# thingy.net
KiCad netlist of a schematic drawn in EAGLE
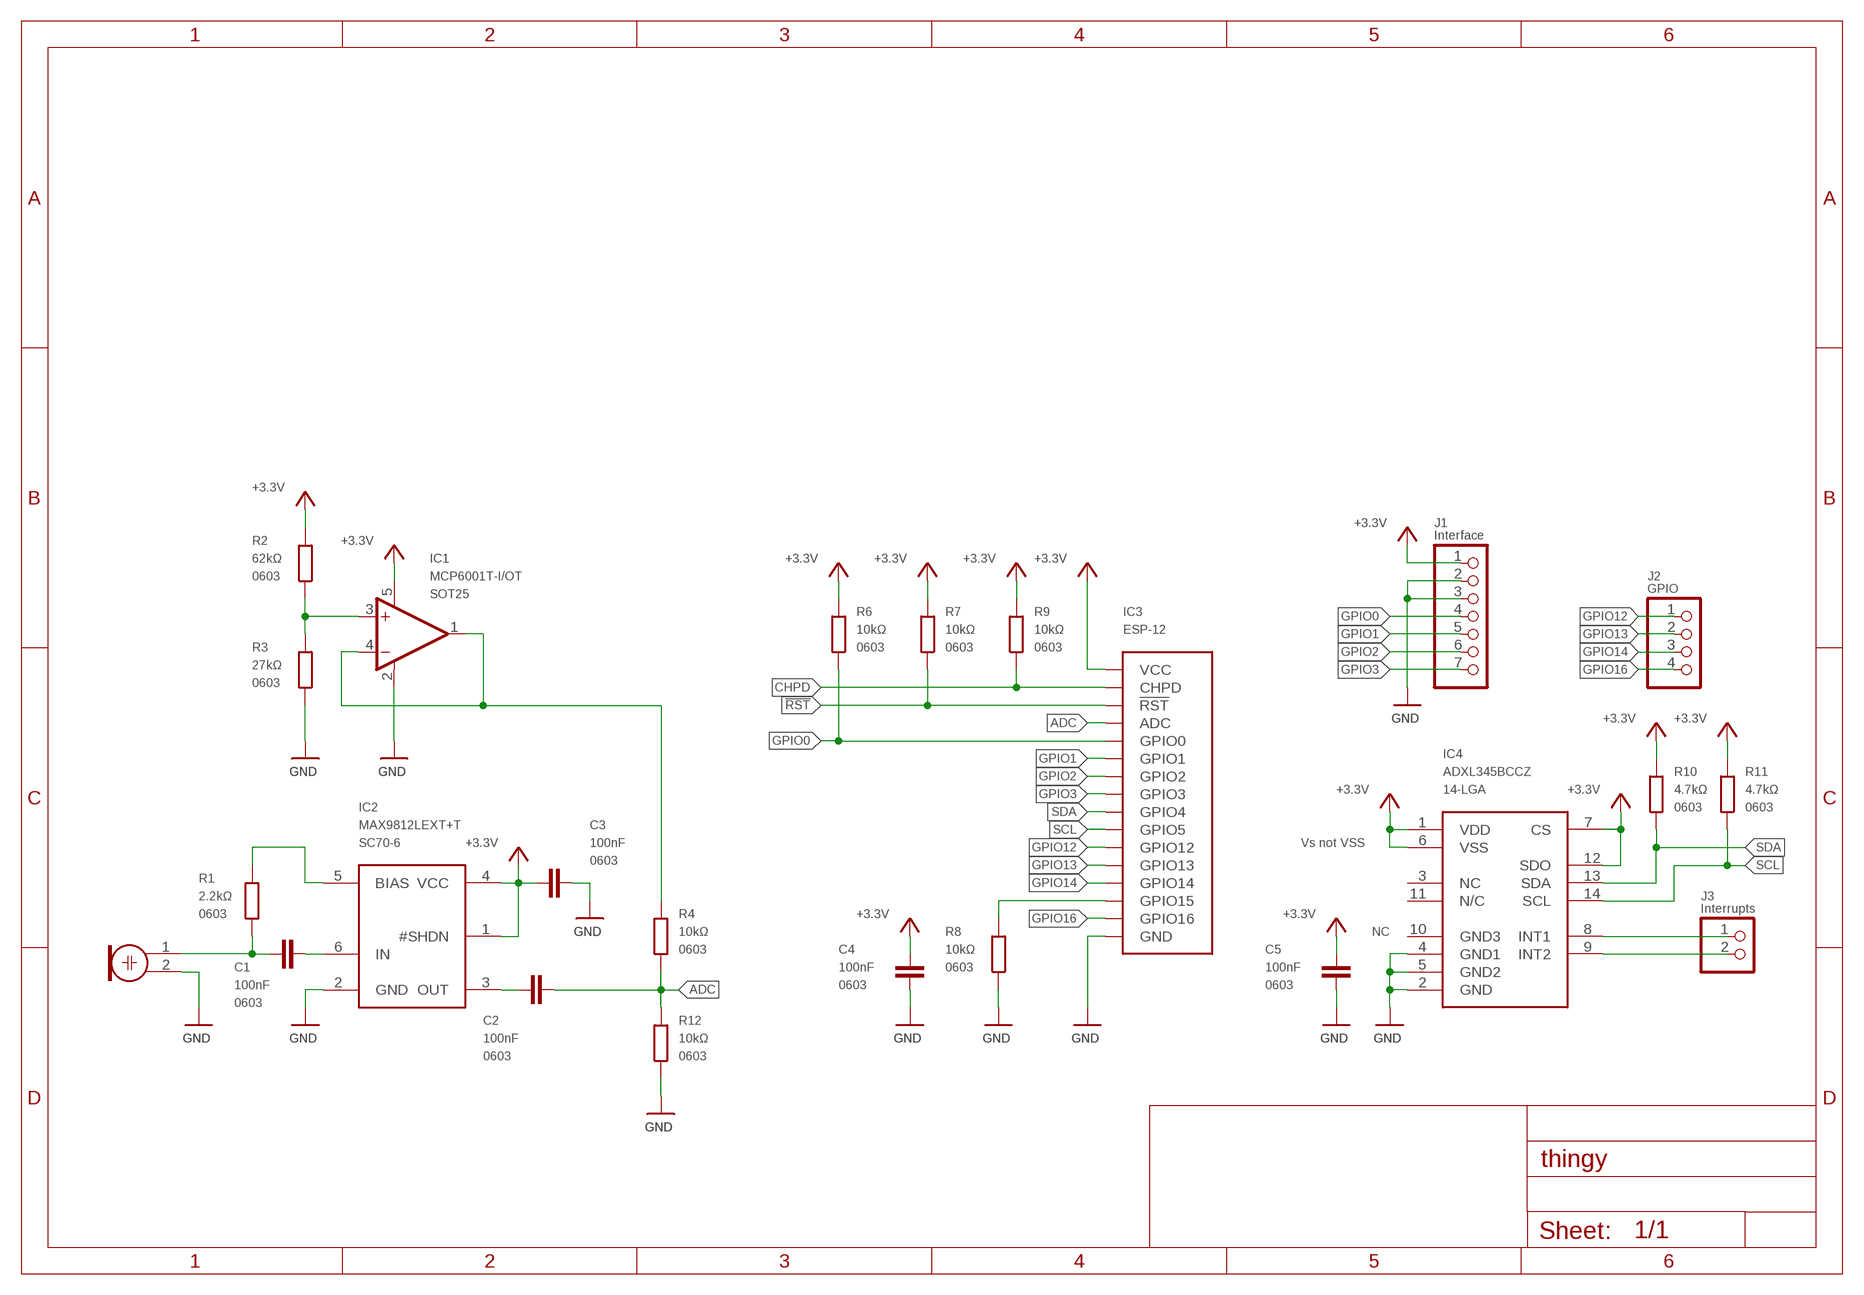
[diagram p0: schematic, sheet 1]

(export (version "E")
  (design (tool "Eeschema 10.0.6"))
  (components
    (comp (ref "C1")
      (value "100nF")
      (footprint "eagle-import:0603")
      (fields (field (name "PACKAGE") "0603"))
      (libsource (lib "eagle-import") (part "C0603"))
    )
    (comp (ref "C2")
      (value "100nF")
      (footprint "eagle-import:0603")
      (fields (field (name "PACKAGE") "0603"))
      (libsource (lib "eagle-import") (part "C0603"))
    )
    (comp (ref "C3")
      (value "100nF")
      (footprint "eagle-import:0603")
      (fields (field (name "PACKAGE") "0603"))
      (libsource (lib "eagle-import") (part "C0603"))
    )
    (comp (ref "C4")
      (value "100nF")
      (footprint "eagle-import:0603")
      (fields (field (name "PACKAGE") "0603"))
      (libsource (lib "eagle-import") (part "C0603"))
    )
    (comp (ref "C5")
      (value "100nF")
      (footprint "eagle-import:0603")
      (fields (field (name "PACKAGE") "0603"))
      (libsource (lib "eagle-import") (part "C0603"))
    )
    (comp (ref "IC1")
      (value "MCP6001T-I/OT")
      (footprint "eagle-import:SOT23-5")
      (fields (field (name "MPN") "OPA340NA/3KG4") (field (name "PACKAGE") "SOT25"))
      (libsource (lib "eagle-import") (part "OPA340N"))
    )
    (comp (ref "IC2")
      (value "MAX9812LEXT+T")
      (footprint "eagle-import:SC-70-6")
      (fields (field (name "PACKAGE") "SC70-6"))
      (libsource (lib "eagle-import") (part "MAX9812"))
    )
    (comp (ref "IC3")
      (value "ESP-12")
      (footprint "eagle-import:ESP-12")
      (libsource (lib "eagle-import") (part "ESP-12"))
    )
    (comp (ref "IC4")
      (value "ADXL345BCCZ")
      (footprint "eagle-import:LGA14")
      (fields (field (name "PACKAGE") "14-LGA"))
      (libsource (lib "eagle-import") (part "ADXL345"))
    )
    (comp (ref "J1")
      (value "Interface")
      (footprint "eagle-import:1X07")
      (libsource (lib "eagle-import") (part "PINHD-1X7"))
    )
    (comp (ref "J2")
      (value "GPIO")
      (footprint "eagle-import:1X04")
      (libsource (lib "eagle-import") (part "PINHD-1X4"))
    )
    (comp (ref "J3")
      (value "Interrupts")
      (footprint "eagle-import:1X02")
      (libsource (lib "eagle-import") (part "PINHD-1X2"))
    )
    (comp (ref "Q1")
      (value "Electret Mic")
      (footprint "eagle-import:WM-64PN")
      (libsource (lib "eagle-import") (part "ELECTRET_MICROPHON-WM.64PN"))
    )
    (comp (ref "R1")
      (value "2.2kΩ")
      (footprint "eagle-import:0603")
      (fields (field (name "PACKAGE") "0603"))
      (libsource (lib "eagle-import") (part "R0603"))
    )
    (comp (ref "R2")
      (value "62kΩ")
      (footprint "eagle-import:0603")
      (fields (field (name "PACKAGE") "0603"))
      (libsource (lib "eagle-import") (part "R0603"))
    )
    (comp (ref "R3")
      (value "27kΩ")
      (footprint "eagle-import:0603")
      (fields (field (name "PACKAGE") "0603"))
      (libsource (lib "eagle-import") (part "R0603"))
    )
    (comp (ref "R4")
      (value "10kΩ")
      (footprint "eagle-import:0603")
      (fields (field (name "PACKAGE") "0603"))
      (libsource (lib "eagle-import") (part "R0603"))
    )
    (comp (ref "R6")
      (value "10kΩ")
      (footprint "eagle-import:0603")
      (fields (field (name "PACKAGE") "0603"))
      (libsource (lib "eagle-import") (part "R0603"))
    )
    (comp (ref "R7")
      (value "10kΩ")
      (footprint "eagle-import:0603")
      (fields (field (name "PACKAGE") "0603"))
      (libsource (lib "eagle-import") (part "R0603"))
    )
    (comp (ref "R8")
      (value "10kΩ")
      (footprint "eagle-import:0603")
      (fields (field (name "PACKAGE") "0603"))
      (libsource (lib "eagle-import") (part "R0603"))
    )
    (comp (ref "R9")
      (value "10kΩ")
      (footprint "eagle-import:0603")
      (fields (field (name "PACKAGE") "0603"))
      (libsource (lib "eagle-import") (part "R0603"))
    )
    (comp (ref "R10")
      (value "4.7kΩ")
      (footprint "eagle-import:0603")
      (fields (field (name "PACKAGE") "0603"))
      (libsource (lib "eagle-import") (part "R0603"))
    )
    (comp (ref "R11")
      (value "4.7kΩ")
      (footprint "eagle-import:0603")
      (fields (field (name "PACKAGE") "0603"))
      (libsource (lib "eagle-import") (part "R0603"))
    )
    (comp (ref "R12")
      (value "10kΩ")
      (footprint "eagle-import:0603")
      (fields (field (name "PACKAGE") "0603"))
      (libsource (lib "eagle-import") (part "R0603"))
    )
  )
  (nets
    (net (code "1") (name "+3.3V") (class "Default")
      (node (ref "C3") (pin "1") (pinfunction "1_1") (pintype "passive"))
      (node (ref "C4") (pin "1") (pinfunction "1_1") (pintype "passive"))
      (node (ref "C5") (pin "1") (pinfunction "1_1") (pintype "passive"))
      (node (ref "IC1") (pin "5") (pinfunction "V+_5") (pintype "power_in"))
      (node (ref "IC2") (pin "1") (pinfunction "#SHDN_1") (pintype "input"))
      (node (ref "IC2") (pin "4") (pinfunction "VCC_4") (pintype "power_in"))
      (node (ref "IC3") (pin "VCC") (pinfunction "VCC_VCC") (pintype "bidirectional"))
      (node (ref "IC4") (pin "1") (pinfunction "VDD_1") (pintype "bidirectional"))
      (node (ref "IC4") (pin "12") (pinfunction "SDO_12") (pintype "bidirectional"))
      (node (ref "IC4") (pin "6") (pinfunction "VSS_6") (pintype "bidirectional"))
      (node (ref "IC4") (pin "7") (pinfunction "CS_7") (pintype "bidirectional"))
      (node (ref "J1") (pin "1") (pinfunction "1_1") (pintype "passive"))
      (node (ref "R10") (pin "2") (pinfunction "2_2") (pintype "passive"))
      (node (ref "R11") (pin "2") (pinfunction "2_2") (pintype "passive"))
      (node (ref "R2") (pin "2") (pinfunction "2_2") (pintype "passive"))
      (node (ref "R6") (pin "2") (pinfunction "2_2") (pintype "passive"))
      (node (ref "R7") (pin "2") (pinfunction "2_2") (pintype "passive"))
      (node (ref "R9") (pin "2") (pinfunction "2_2") (pintype "passive"))
    )
    (net (code "2") (name "/GND") (class "Default")
      (node (ref "C3") (pin "2") (pinfunction "2_2") (pintype "passive"))
      (node (ref "C4") (pin "2") (pinfunction "2_2") (pintype "passive"))
      (node (ref "C5") (pin "2") (pinfunction "2_2") (pintype "passive"))
      (node (ref "IC1") (pin "2") (pinfunction "V-_2") (pintype "power_in"))
      (node (ref "IC2") (pin "2") (pinfunction "GND_2") (pintype "power_in"))
      (node (ref "IC3") (pin "GND") (pinfunction "GND_GND") (pintype "bidirectional"))
      (node (ref "IC4") (pin "2") (pinfunction "GND_2") (pintype "bidirectional"))
      (node (ref "IC4") (pin "4") (pinfunction "GND1_4") (pintype "bidirectional"))
      (node (ref "IC4") (pin "5") (pinfunction "GND2_5") (pintype "bidirectional"))
      (node (ref "J1") (pin "2") (pinfunction "2_2") (pintype "passive"))
      (node (ref "J1") (pin "3") (pinfunction "3_3") (pintype "passive"))
      (node (ref "Q1") (pin "2") (pinfunction "2_2") (pintype "passive"))
      (node (ref "R12") (pin "1") (pinfunction "1_1") (pintype "passive"))
      (node (ref "R3") (pin "1") (pinfunction "1_1") (pintype "passive"))
      (node (ref "R8") (pin "1") (pinfunction "1_1") (pintype "passive"))
    )
    (net (code "3") (name "/~{RST}") (class "Default")
      (node (ref "IC3") (pin "RST") (pinfunction "~{RST}_RST") (pintype "bidirectional"))
      (node (ref "R7") (pin "1") (pinfunction "1_1") (pintype "passive"))
    )
    (net (code "4") (name "ADC") (class "Default")
      (node (ref "C2") (pin "2") (pinfunction "2_2") (pintype "passive"))
      (node (ref "IC3") (pin "ADC") (pinfunction "ADC_ADC") (pintype "bidirectional"))
      (node (ref "R12") (pin "2") (pinfunction "2_2") (pintype "passive"))
      (node (ref "R4") (pin "1") (pinfunction "1_1") (pintype "passive"))
    )
    (net (code "5") (name "CHPD") (class "Default")
      (node (ref "IC3") (pin "CHPD") (pinfunction "CHPD_CHPD") (pintype "bidirectional"))
      (node (ref "R9") (pin "1") (pinfunction "1_1") (pintype "passive"))
    )
    (net (code "6") (name "GPIO0") (class "Default")
      (node (ref "IC3") (pin "GPIO0") (pinfunction "GPIO0_GPIO0") (pintype "bidirectional"))
      (node (ref "J1") (pin "4") (pinfunction "4_4") (pintype "passive"))
      (node (ref "R6") (pin "1") (pinfunction "1_1") (pintype "passive"))
    )
    (net (code "7") (name "GPIO1") (class "Default")
      (node (ref "IC3") (pin "GPIO1") (pinfunction "GPIO1_GPIO1") (pintype "bidirectional"))
      (node (ref "J1") (pin "5") (pinfunction "5_5") (pintype "passive"))
    )
    (net (code "8") (name "GPIO2") (class "Default")
      (node (ref "IC3") (pin "GPIO2") (pinfunction "GPIO2_GPIO2") (pintype "bidirectional"))
      (node (ref "J1") (pin "6") (pinfunction "6_6") (pintype "passive"))
    )
    (net (code "9") (name "GPIO3") (class "Default")
      (node (ref "IC3") (pin "GPIO3") (pinfunction "GPIO3_GPIO3") (pintype "bidirectional"))
      (node (ref "J1") (pin "7") (pinfunction "7_7") (pintype "passive"))
    )
    (net (code "10") (name "GPIO12") (class "Default")
      (node (ref "IC3") (pin "GPIO12") (pinfunction "GPIO12_GPIO12") (pintype "bidirectional"))
      (node (ref "J2") (pin "1") (pinfunction "1_1") (pintype "passive"))
    )
    (net (code "11") (name "GPIO13") (class "Default")
      (node (ref "IC3") (pin "GPIO13") (pinfunction "GPIO13_GPIO13") (pintype "bidirectional"))
      (node (ref "J2") (pin "2") (pinfunction "2_2") (pintype "passive"))
    )
    (net (code "12") (name "GPIO14") (class "Default")
      (node (ref "IC3") (pin "GPIO14") (pinfunction "GPIO14_GPIO14") (pintype "bidirectional"))
      (node (ref "J2") (pin "3") (pinfunction "3_3") (pintype "passive"))
    )
    (net (code "13") (name "GPIO16") (class "Default")
      (node (ref "IC3") (pin "GPIO16") (pinfunction "GPIO16_GPIO16") (pintype "bidirectional"))
      (node (ref "J2") (pin "4") (pinfunction "4_4") (pintype "passive"))
    )
    (net (code "14") (name "Net-(C1-Pad1)") (class "Default")
      (node (ref "C1") (pin "1") (pinfunction "1_1") (pintype "passive"))
      (node (ref "Q1") (pin "1") (pinfunction "1_1") (pintype "passive"))
      (node (ref "R1") (pin "1") (pinfunction "1_1") (pintype "passive"))
    )
    (net (code "15") (name "Net-(IC1-+IN)") (class "Default")
      (node (ref "IC1") (pin "3") (pinfunction "+IN_3") (pintype "input"))
      (node (ref "R2") (pin "1") (pinfunction "1_1") (pintype "passive"))
      (node (ref "R3") (pin "2") (pinfunction "2_2") (pintype "passive"))
    )
    (net (code "16") (name "Net-(IC1--IN)") (class "Default")
      (node (ref "IC1") (pin "1") (pinfunction "OUT_1") (pintype "output"))
      (node (ref "IC1") (pin "4") (pinfunction "-IN_4") (pintype "input"))
      (node (ref "R4") (pin "2") (pinfunction "2_2") (pintype "passive"))
    )
    (net (code "17") (name "Net-(IC2-BIAS)") (class "Default")
      (node (ref "IC2") (pin "5") (pinfunction "BIAS_5") (pintype "input"))
      (node (ref "R1") (pin "2") (pinfunction "2_2") (pintype "passive"))
    )
    (net (code "18") (name "Net-(IC2-IN)") (class "Default")
      (node (ref "C1") (pin "2") (pinfunction "2_2") (pintype "passive"))
      (node (ref "IC2") (pin "6") (pinfunction "IN_6") (pintype "input"))
    )
    (net (code "19") (name "Net-(IC2-OUT)") (class "Default")
      (node (ref "C2") (pin "1") (pinfunction "1_1") (pintype "passive"))
      (node (ref "IC2") (pin "3") (pinfunction "OUT_3") (pintype "output"))
    )
    (net (code "20") (name "Net-(IC3-PadGPIO15)") (class "Default")
      (node (ref "IC3") (pin "GPIO15") (pinfunction "GPIO15_GPIO15") (pintype "bidirectional"))
      (node (ref "R8") (pin "2") (pinfunction "2_2") (pintype "passive"))
    )
    (net (code "21") (name "Net-(IC4-INT1)") (class "Default")
      (node (ref "IC4") (pin "8") (pinfunction "INT1_8") (pintype "bidirectional"))
      (node (ref "J3") (pin "1") (pinfunction "1_1") (pintype "passive"))
    )
    (net (code "22") (name "Net-(IC4-INT2)") (class "Default")
      (node (ref "IC4") (pin "9") (pinfunction "INT2_9") (pintype "bidirectional"))
      (node (ref "J3") (pin "2") (pinfunction "2_2") (pintype "passive"))
    )
    (net (code "23") (name "SCL") (class "Default")
      (node (ref "IC3") (pin "GPIO5") (pinfunction "GPIO5_GPIO5") (pintype "bidirectional"))
      (node (ref "IC4") (pin "14") (pinfunction "SCL_14") (pintype "bidirectional"))
      (node (ref "R11") (pin "1") (pinfunction "1_1") (pintype "passive"))
    )
    (net (code "24") (name "SDA") (class "Default")
      (node (ref "IC3") (pin "GPIO4") (pinfunction "GPIO4_GPIO4") (pintype "bidirectional"))
      (node (ref "IC4") (pin "13") (pinfunction "SDA_13") (pintype "bidirectional"))
      (node (ref "R10") (pin "1") (pinfunction "1_1") (pintype "passive"))
    )
    (net (code "25") (name "unconnected-(IC4-GND3-Pad10)") (class "Default")
      (node (ref "IC4") (pin "10") (pinfunction "GND3_10") (pintype "bidirectional"))
    )
    (net (code "26") (name "unconnected-(IC4-NC-Pad3)") (class "Default")
      (node (ref "IC4") (pin "3") (pinfunction "NC_3") (pintype "bidirectional"))
    )
    (net (code "27") (name "unconnected-(IC4-N{slash}C-Pad11)") (class "Default")
      (node (ref "IC4") (pin "11") (pinfunction "N/C_11") (pintype "bidirectional"))
    )
  )
)
